# uncoupler-decoder.net
KiCad netlist of a schematic drawn in EAGLE
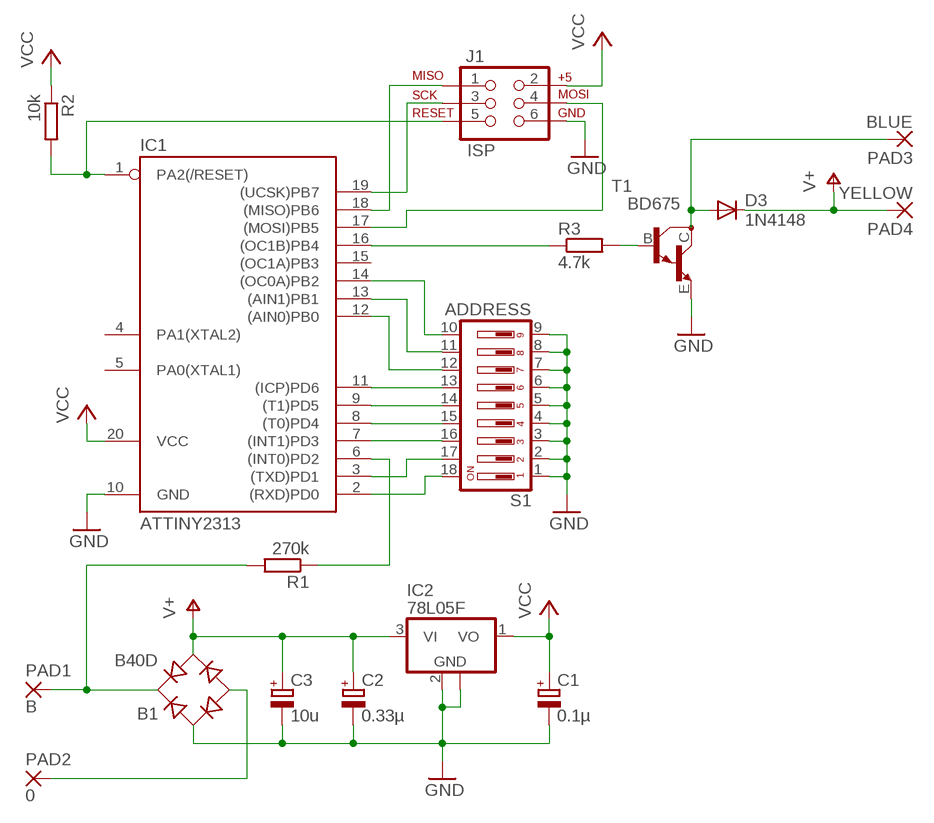
[diagram p0: schematic, sheet 1]

(export (version "E")
  (design (tool "Eeschema 10.0.6"))
  (components
    (comp (ref "B1")
      (value "B40D")
      (footprint "eagle-import:B40S")
      (libsource (lib "eagle-import") (part "RECTIFIER-B40S"))
    )
    (comp (ref "C1")
      (value "0.1µ")
      (footprint "eagle-import:A_3216-18R")
      (libsource (lib "eagle-import") (part "CPOL-EUA/3216-18R"))
    )
    (comp (ref "C2")
      (value "0.33µ")
      (footprint "eagle-import:A_3216-18R")
      (libsource (lib "eagle-import") (part "CPOL-EUA/3216-18R"))
    )
    (comp (ref "C3")
      (value "10u")
      (footprint "eagle-import:CT6032")
      (libsource (lib "eagle-import") (part "CPOL-EUCT6032"))
    )
    (comp (ref "D3")
      (value "1N4148")
      (footprint "eagle-import:SOD323-R")
      (libsource (lib "eagle-import") (part "DIODE-SOD323-R"))
    )
    (comp (ref "IC1")
      (value "ATTINY2313")
      (footprint "eagle-import:SO20L$")
      (libsource (lib "eagle-import") (part "TINY2313-S"))
    )
    (comp (ref "IC2")
      (value "78L05F")
      (footprint "eagle-import:SOT89")
      (libsource (lib "eagle-import") (part "78LF05"))
    )
    (comp (ref "J1")
      (value "ISP")
      (footprint "eagle-import:ISP-ADAPTER-SMD")
      (libsource (lib "eagle-import") (part "AVR_ISPAVX9188MATINGGUIDE"))
    )
    (comp (ref "PAD1")
      (value "B")
      (footprint "eagle-import:SMD1,27-2,54")
      (libsource (lib "eagle-import") (part "SMD2"))
    )
    (comp (ref "PAD2")
      (value "0")
      (footprint "eagle-import:SMD1,27-2,54")
      (libsource (lib "eagle-import") (part "SMD2"))
    )
    (comp (ref "PAD3")
      (value "BLUE")
      (footprint "eagle-import:SMD1,27-2,54")
      (libsource (lib "eagle-import") (part "SMD2"))
    )
    (comp (ref "PAD4")
      (value "YELLOW")
      (footprint "eagle-import:SMD1,27-2,54")
      (libsource (lib "eagle-import") (part "SMD2"))
    )
    (comp (ref "R1")
      (value "270k")
      (footprint "eagle-import:R0805")
      (libsource (lib "eagle-import") (part "R-EU_R0805"))
    )
    (comp (ref "R2")
      (value "10k")
      (footprint "eagle-import:R0805")
      (libsource (lib "eagle-import") (part "R-EU_R0805"))
    )
    (comp (ref "R3")
      (value "4.7k")
      (footprint "eagle-import:R0805")
      (libsource (lib "eagle-import") (part "R-EU_R0805"))
    )
    (comp (ref "S1")
      (value "ADDRESS")
      (footprint "eagle-import:CTS-219-09")
      (libsource (lib "eagle-import") (part "219-09"))
    )
    (comp (ref "T1")
      (value "BD675")
      (footprint "eagle-import:SOT23-BEC")
      (libsource (lib "eagle-import") (part "-NPN_DARL-SOT23-BECMMBTA13LT1"))
    )
  )
  (nets
    (net (code "1") (name "GND") (class "Default")
      (node (ref "B1") (pin "AC1") (pinfunction "AC1_AC1") (pintype "passive"))
      (node (ref "C1") (pin "-") (pinfunction "-_-") (pintype "passive"))
      (node (ref "C2") (pin "-") (pinfunction "-_-") (pintype "passive"))
      (node (ref "C3") (pin "-") (pinfunction "-_-") (pintype "passive"))
      (node (ref "IC1") (pin "10") (pinfunction "GND_10") (pintype "power_in"))
      (node (ref "IC2") (pin "2") (pinfunction "GND_2") (pintype "passive"))
      (node (ref "IC2") (pin "2@1") (pinfunction "GND_2@1") (pintype "passive"))
      (node (ref "J1") (pin "6") (pinfunction "6_6") (pintype "passive"))
      (node (ref "S1") (pin "1") (pinfunction "1_1") (pintype "passive"))
      (node (ref "S1") (pin "2") (pinfunction "2_2") (pintype "passive"))
      (node (ref "S1") (pin "3") (pinfunction "3_3") (pintype "passive"))
      (node (ref "S1") (pin "4") (pinfunction "4_4") (pintype "passive"))
      (node (ref "S1") (pin "5") (pinfunction "5_5") (pintype "passive"))
      (node (ref "S1") (pin "6") (pinfunction "6_6") (pintype "passive"))
      (node (ref "S1") (pin "7") (pinfunction "7_7") (pintype "passive"))
      (node (ref "S1") (pin "8") (pinfunction "8_8") (pintype "passive"))
      (node (ref "S1") (pin "9") (pinfunction "9_9") (pintype "passive"))
      (node (ref "T1") (pin "E") (pinfunction "E_E") (pintype "passive"))
    )
    (net (code "2") (name "Net-(IC1-(AIN0)PB0)") (class "Default")
      (node (ref "IC1") (pin "12") (pinfunction "(AIN0)PB0_12") (pintype "bidirectional"))
      (node (ref "S1") (pin "12") (pinfunction "12_12") (pintype "passive"))
    )
    (net (code "3") (name "Net-(IC1-(AIN1)PB1)") (class "Default")
      (node (ref "IC1") (pin "13") (pinfunction "(AIN1)PB1_13") (pintype "bidirectional"))
      (node (ref "S1") (pin "11") (pinfunction "11_11") (pintype "passive"))
    )
    (net (code "4") (name "Net-(IC1-(ICP)PD6)") (class "Default")
      (node (ref "IC1") (pin "11") (pinfunction "(ICP)PD6_11") (pintype "bidirectional"))
      (node (ref "S1") (pin "13") (pinfunction "13_13") (pintype "passive"))
    )
    (net (code "5") (name "Net-(IC1-(INT0)PD2)") (class "Default")
      (node (ref "IC1") (pin "6") (pinfunction "(INT0)PD2_6") (pintype "bidirectional"))
      (node (ref "R1") (pin "1") (pinfunction "1_1") (pintype "passive"))
    )
    (net (code "6") (name "Net-(IC1-(INT1)PD3)") (class "Default")
      (node (ref "IC1") (pin "7") (pinfunction "(INT1)PD3_7") (pintype "bidirectional"))
      (node (ref "S1") (pin "16") (pinfunction "16_16") (pintype "passive"))
    )
    (net (code "7") (name "Net-(IC1-(MISO)PB6)") (class "Default")
      (node (ref "IC1") (pin "18") (pinfunction "(MISO)PB6_18") (pintype "bidirectional"))
      (node (ref "J1") (pin "1") (pinfunction "1_1") (pintype "passive"))
    )
    (net (code "8") (name "Net-(IC1-(MOSI)PB5)") (class "Default")
      (node (ref "IC1") (pin "17") (pinfunction "(MOSI)PB5_17") (pintype "bidirectional"))
      (node (ref "J1") (pin "4") (pinfunction "4_4") (pintype "passive"))
    )
    (net (code "9") (name "Net-(IC1-(OC0A)PB2)") (class "Default")
      (node (ref "IC1") (pin "14") (pinfunction "(OC0A)PB2_14") (pintype "bidirectional"))
      (node (ref "S1") (pin "10") (pinfunction "10_10") (pintype "passive"))
    )
    (net (code "10") (name "Net-(IC1-(OC1B)PB4)") (class "Default")
      (node (ref "IC1") (pin "16") (pinfunction "(OC1B)PB4_16") (pintype "bidirectional"))
      (node (ref "R3") (pin "1") (pinfunction "1_1") (pintype "passive"))
    )
    (net (code "11") (name "Net-(IC1-(RXD)PD0)") (class "Default")
      (node (ref "IC1") (pin "2") (pinfunction "(RXD)PD0_2") (pintype "bidirectional"))
      (node (ref "S1") (pin "18") (pinfunction "18_18") (pintype "passive"))
    )
    (net (code "12") (name "Net-(IC1-(T0)PD4)") (class "Default")
      (node (ref "IC1") (pin "8") (pinfunction "(T0)PD4_8") (pintype "bidirectional"))
      (node (ref "S1") (pin "15") (pinfunction "15_15") (pintype "passive"))
    )
    (net (code "13") (name "Net-(IC1-(T1)PD5)") (class "Default")
      (node (ref "IC1") (pin "9") (pinfunction "(T1)PD5_9") (pintype "bidirectional"))
      (node (ref "S1") (pin "14") (pinfunction "14_14") (pintype "passive"))
    )
    (net (code "14") (name "Net-(IC1-(TXD)PD1)") (class "Default")
      (node (ref "IC1") (pin "3") (pinfunction "(TXD)PD1_3") (pintype "bidirectional"))
      (node (ref "S1") (pin "17") (pinfunction "17_17") (pintype "passive"))
    )
    (net (code "15") (name "Net-(IC1-(UCSK)PB7)") (class "Default")
      (node (ref "IC1") (pin "19") (pinfunction "(UCSK)PB7_19") (pintype "bidirectional"))
      (node (ref "J1") (pin "3") (pinfunction "3_3") (pintype "passive"))
    )
    (net (code "16") (name "Net-(IC1-PA2({slash}RESET))") (class "Default")
      (node (ref "IC1") (pin "1") (pinfunction "PA2(/RESET)_1") (pintype "input"))
      (node (ref "J1") (pin "5") (pinfunction "5_5") (pintype "passive"))
      (node (ref "R2") (pin "2") (pinfunction "2_2") (pintype "passive"))
    )
    (net (code "17") (name "Net-(PAD1-P)") (class "Default")
      (node (ref "B1") (pin "+") (pinfunction "+_+") (pintype "passive"))
      (node (ref "PAD1") (pin "1") (pinfunction "P_1") (pintype "passive"))
      (node (ref "R1") (pin "2") (pinfunction "2_2") (pintype "passive"))
    )
    (net (code "18") (name "Net-(PAD2-P)") (class "Default")
      (node (ref "B1") (pin "-") (pinfunction "-_-") (pintype "passive"))
      (node (ref "PAD2") (pin "1") (pinfunction "P_1") (pintype "passive"))
    )
    (net (code "19") (name "Net-(PAD3-P)") (class "Default")
      (node (ref "D3") (pin "A") (pinfunction "A_A") (pintype "passive"))
      (node (ref "PAD3") (pin "1") (pinfunction "P_1") (pintype "passive"))
      (node (ref "T1") (pin "C") (pinfunction "C_C") (pintype "passive"))
    )
    (net (code "20") (name "Net-(R3-Pad2)") (class "Default")
      (node (ref "R3") (pin "2") (pinfunction "2_2") (pintype "passive"))
      (node (ref "T1") (pin "B") (pinfunction "B_B") (pintype "passive"))
    )
    (net (code "21") (name "V+") (class "Default")
      (node (ref "B1") (pin "AC2") (pinfunction "AC2_AC2") (pintype "passive"))
      (node (ref "C2") (pin "+") (pinfunction "+_+") (pintype "passive"))
      (node (ref "C3") (pin "+") (pinfunction "+_+") (pintype "passive"))
      (node (ref "D3") (pin "C") (pinfunction "C_C") (pintype "passive"))
      (node (ref "IC2") (pin "3") (pinfunction "VI_3") (pintype "input"))
      (node (ref "PAD4") (pin "1") (pinfunction "P_1") (pintype "passive"))
    )
    (net (code "22") (name "VCC") (class "Default")
      (node (ref "C1") (pin "+") (pinfunction "+_+") (pintype "passive"))
      (node (ref "IC1") (pin "20") (pinfunction "VCC_20") (pintype "power_in"))
      (node (ref "IC2") (pin "1") (pinfunction "VO_1") (pintype "passive"))
      (node (ref "J1") (pin "2") (pinfunction "2_2") (pintype "passive"))
      (node (ref "R2") (pin "1") (pinfunction "1_1") (pintype "passive"))
    )
    (net (code "23") (name "unconnected-(IC1-(OC1A)PB3-Pad15)") (class "Default")
      (node (ref "IC1") (pin "15") (pinfunction "(OC1A)PB3_15") (pintype "bidirectional"))
    )
    (net (code "24") (name "unconnected-(IC1-PA0(XTAL1)-Pad5)") (class "Default")
      (node (ref "IC1") (pin "5") (pinfunction "PA0(XTAL1)_5") (pintype "bidirectional"))
    )
    (net (code "25") (name "unconnected-(IC1-PA1(XTAL2)-Pad4)") (class "Default")
      (node (ref "IC1") (pin "4") (pinfunction "PA1(XTAL2)_4") (pintype "bidirectional"))
    )
  )
)
